# S7CAS-PLEIADES-CARTE-MERE_P01_ETHERNET.net
KiCad netlist of a schematic drawn in Altium Designer
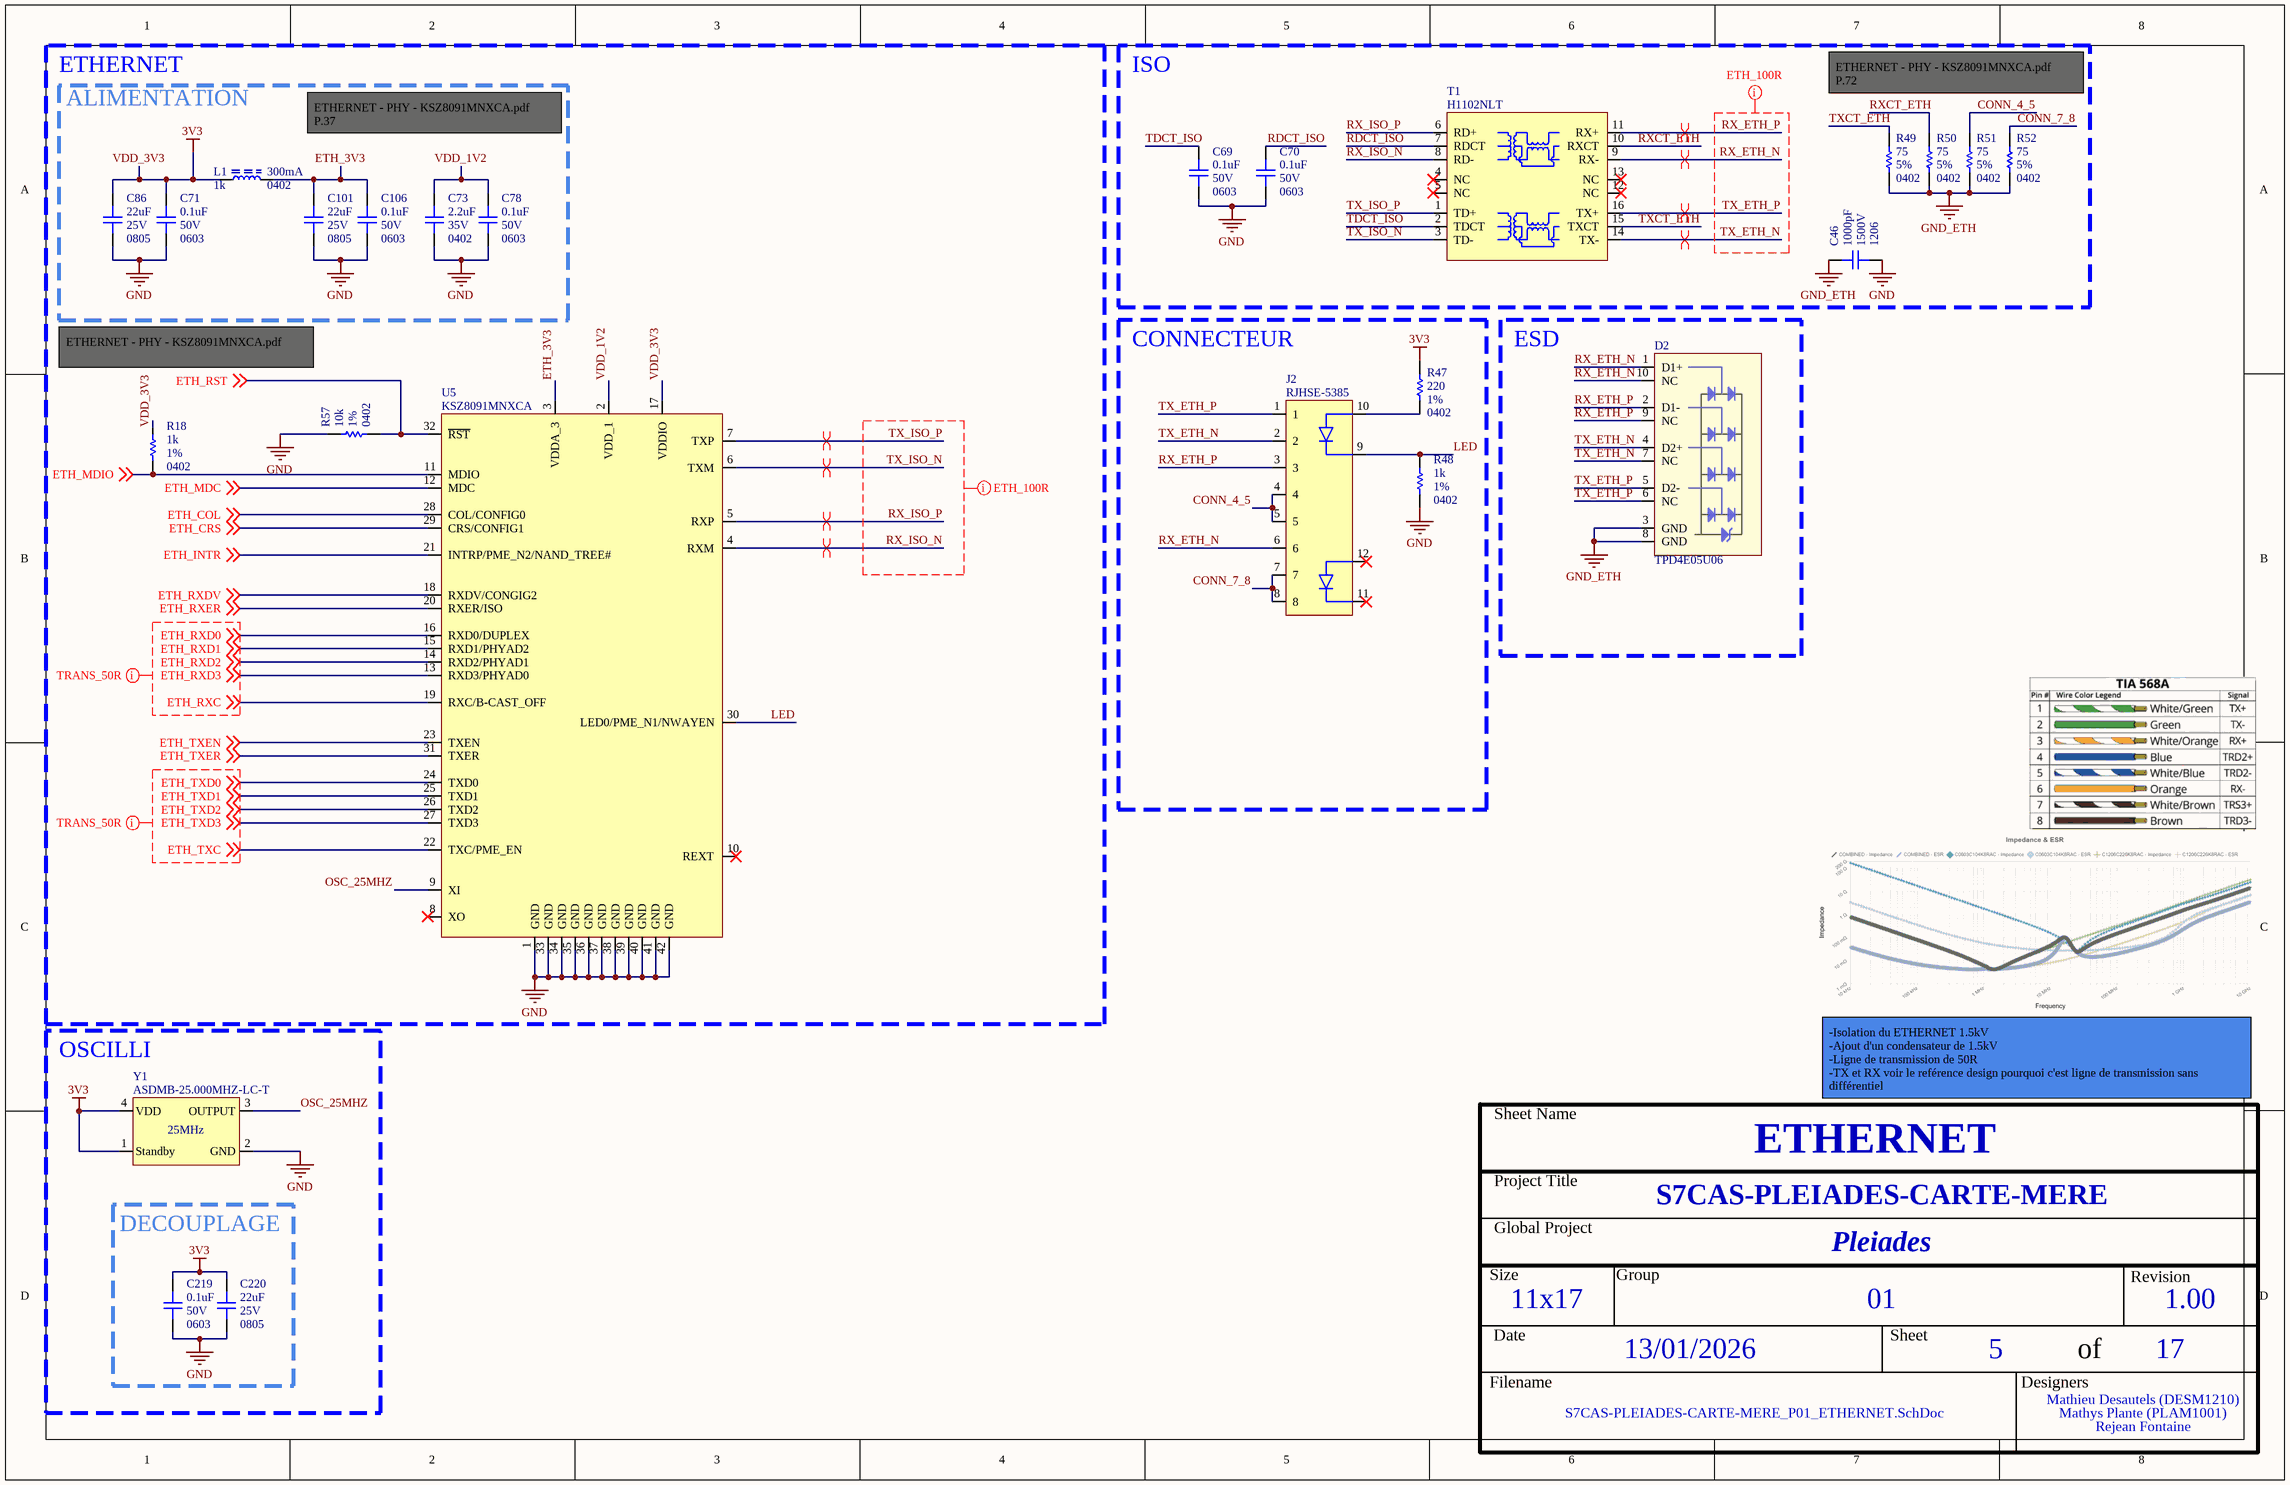
[diagram p0: S7CAS-PLEIADES-CARTE-MERE_P01_ETHERNET.SchDoc]

(export (version "E")
  (design (tool "Eeschema 10.0.6"))
  (components
    (comp (ref "C46")
      (value "1000pF")
      (footprint "CAP_1206")
      (description "1000 pF ±5% 1500V (1.5kV) Ceramic Capacitor C0G, NP0 1206 (3216 Metric)")
      (fields
        (field (name "MFG") "Vishay Vitramon")
        (field (name "MFG PART NUMBER") "VJ1206A102JXRAT5Z")
        (field (name "VOLTAGE") "1500V")
        (field (name "PACKAGE") "1206")
        (field (name "CREATEDBY") "Jonathan Bouchard")
      )
      (libsource (lib "s7cas_lib2023") (part "CAP - 1206"))
    )
    (comp (ref "C69")
      (value "0.1uF")
      (footprint "CAP_0603")
      (description "0.1 µF ±10% 50V Ceramic Capacitor X7R 0603 (1608 Metric)")
      (fields
        (field (name "MFG") "KEMET")
        (field (name "MFG PART NUMBER") "C0603C104K5RACTU")
        (field (name "VOLTAGE") "50V")
        (field (name "PACKAGE") "0603")
        (field (name "CREATEDBY") "Jonathan Bouchard")
      )
      (libsource (lib "s7cas_lib2023") (part "CAP - 0603"))
    )
    (comp (ref "C70")
      (value "0.1uF")
      (footprint "CAP_0603")
      (description "0.1 µF ±10% 50V Ceramic Capacitor X7R 0603 (1608 Metric)")
      (fields
        (field (name "MFG") "KEMET")
        (field (name "MFG PART NUMBER") "C0603C104K5RACTU")
        (field (name "VOLTAGE") "50V")
        (field (name "PACKAGE") "0603")
        (field (name "CREATEDBY") "Jonathan Bouchard")
      )
      (libsource (lib "s7cas_lib2023") (part "CAP - 0603"))
    )
    (comp (ref "C71")
      (value "0.1uF")
      (footprint "CAP_0603")
      (description "0.1 µF ±10% 50V Ceramic Capacitor X7R 0603 (1608 Metric)")
      (fields
        (field (name "MFG") "KEMET")
        (field (name "MFG PART NUMBER") "C0603C104K5RACTU")
        (field (name "VOLTAGE") "50V")
        (field (name "PACKAGE") "0603")
        (field (name "CREATEDBY") "Jonathan Bouchard")
      )
      (libsource (lib "s7cas_lib2023") (part "CAP - 0603"))
    )
    (comp (ref "C73")
      (value "2.2uF")
      (footprint "CAP_0402")
      (description "2.2 µF ±10% 35V Ceramic Capacitor X5R 0402 (1005 Metric)")
      (fields
        (field (name "MFG") "Murata Electronics")
        (field (name "MFG PART NUMBER") "GRM155R6YA225KE11D")
        (field (name "VOLTAGE") "35V")
        (field (name "PACKAGE") "0402")
        (field (name "CREATEDBY") "Jonathan Bouchard")
      )
      (libsource (lib "s7cas_lib2023") (part "CAP - 0402"))
    )
    (comp (ref "C78")
      (value "0.1uF")
      (footprint "CAP_0603")
      (description "0.1 µF ±10% 50V Ceramic Capacitor X7R 0603 (1608 Metric)")
      (fields
        (field (name "MFG") "KEMET")
        (field (name "MFG PART NUMBER") "C0603C104K5RACTU")
        (field (name "VOLTAGE") "50V")
        (field (name "PACKAGE") "0603")
        (field (name "CREATEDBY") "Jonathan Bouchard")
      )
      (libsource (lib "s7cas_lib2023") (part "CAP - 0603"))
    )
    (comp (ref "C86")
      (value "22uF")
      (footprint "CAP_0805")
      (description "22 µF ±20% 25V Ceramic Capacitor X5R 0805 (2012 Metric)")
      (fields
        (field (name "MFG") "Samsung Electro-Mechanics")
        (field (name "MFG PART NUMBER") "CL21A226MAYNNNE")
        (field (name "VOLTAGE") "25V")
        (field (name "PACKAGE") "0805")
        (field (name "CREATEDBY") "Jonathan Bouchard")
      )
      (libsource (lib "s7cas_lib2023") (part "CAP - 0805"))
    )
    (comp (ref "C101")
      (value "22uF")
      (footprint "CAP_0805")
      (description "22 µF ±20% 25V Ceramic Capacitor X5R 0805 (2012 Metric)")
      (fields
        (field (name "MFG") "Samsung Electro-Mechanics")
        (field (name "MFG PART NUMBER") "CL21A226MAYNNNE")
        (field (name "VOLTAGE") "25V")
        (field (name "PACKAGE") "0805")
        (field (name "CREATEDBY") "Jonathan Bouchard")
      )
      (libsource (lib "s7cas_lib2023") (part "CAP - 0805"))
    )
    (comp (ref "C106")
      (value "0.1uF")
      (footprint "CAP_0603")
      (description "0.1 µF ±10% 50V Ceramic Capacitor X7R 0603 (1608 Metric)")
      (fields
        (field (name "MFG") "KEMET")
        (field (name "MFG PART NUMBER") "C0603C104K5RACTU")
        (field (name "VOLTAGE") "50V")
        (field (name "PACKAGE") "0603")
        (field (name "CREATEDBY") "Jonathan Bouchard")
      )
      (libsource (lib "s7cas_lib2023") (part "CAP - 0603"))
    )
    (comp (ref "C219")
      (value "0.1uF")
      (footprint "CAP_0603")
      (description "0.1 µF ±10% 50V Ceramic Capacitor X7R 0603 (1608 Metric)")
      (fields
        (field (name "MFG") "KEMET")
        (field (name "MFG PART NUMBER") "C0603C104K5RACTU")
        (field (name "VOLTAGE") "50V")
        (field (name "PACKAGE") "0603")
        (field (name "CREATEDBY") "Jonathan Bouchard")
      )
      (libsource (lib "s7cas_lib2023") (part "CAP - 0603"))
    )
    (comp (ref "C220")
      (value "22uF")
      (footprint "CAP_0805")
      (description "22 µF ±20% 25V Ceramic Capacitor X5R 0805 (2012 Metric)")
      (fields
        (field (name "MFG") "Samsung Electro-Mechanics")
        (field (name "MFG PART NUMBER") "CL21A226MAYNNNE")
        (field (name "VOLTAGE") "25V")
        (field (name "PACKAGE") "0805")
        (field (name "CREATEDBY") "Jonathan Bouchard")
      )
      (libsource (lib "s7cas_lib2023") (part "CAP - 0805"))
    )
    (comp (ref "D2")
      (value "TPD4E05U06")
      (footprint "TVS_DATA_TPD4E05U06")
      (description "TVS - TVS DIODE 5.5VWM 14VC - 10SON")
      (fields
        (field (name "MFG PART NUMBER") "TPD4E05U06DQAR")
        (field (name "CREATEDBY/DATE") "Olivier Bernard / 12/3/2018")
        (field (name "VERIFIEDBY") "Caroline Paulin / 4 juillet 2018")
      )
      (libsource (lib "s7cas_lib2023") (part "TVS_DATA_TPD4E05U06"))
    )
    (comp (ref "J2")
      (value "RJHSE-5385")
      (footprint "CONN_ETHERNET_RJHSE-5385")
      (description "CONN - MOD JACK RJ45 R/A ETHERNET - TH")
      (fields (field (name "MFG") "Amphenol") (field (name "CREATEDBY") "Jonathan Bouchard"))
      (libsource (lib "s7cas_lib2023") (part "CONN_ETHERNET_RJHSE-5385"))
    )
    (comp (ref "L1")
      (value "1k")
      (footprint "FER_0402")
      (description "1 kOhms @ 100 MHz 1 Ferrite Bead 0402 (1005 Metric) 300mA 650mOhm")
      (fields
        (field (name "MFG") "Murata Electronics")
        (field (name "MFG PART NUMBER") "BLM15AG102SN1D")
        (field (name "CURRENT") "300mA")
        (field (name "PACKAGE") "0402")
        (field (name "CREATEDBY") "Jonathan Bouchard")
      )
      (libsource (lib "s7cas_lib2023") (part "FER - 0402"))
    )
    (comp (ref "R18")
      (value "1k")
      (footprint "RES_0402")
      (description "1 kOhms ±1% 0.1W, 1/10W Chip Resistor 0402 (1005 Metric) Automotive AEC-Q200 Thick Film")
      (fields
        (field (name "VOLTAGE") "50V")
        (field (name "MFG") "Panasonic Electronic Components")
        (field (name "PACKAGE") "0402")
        (field (name "PRECISION") "1%")
        (field (name "CREATEDBY") "Jonathan Bouchard")
      )
      (libsource (lib "s7cas_lib2023") (part "RES - 0402"))
    )
    (comp (ref "R47")
      (value "220")
      (footprint "RES_0402")
      (description "220 Ohms ±1% 0.1W, 1/10W Chip Resistor 0402 (1005 Metric) Automotive AEC-Q200 Thick Film220")
      (fields
        (field (name "VOLTAGE") "50V")
        (field (name "MFG") "Panasonic Electronic Components")
        (field (name "PACKAGE") "0402")
        (field (name "PRECISION") "1%")
        (field (name "CREATEDBY") "Jonathan Bouchard")
      )
      (libsource (lib "s7cas_lib2023") (part "RES - 0402"))
    )
    (comp (ref "R48")
      (value "1k")
      (footprint "RES_0402")
      (description "1 kOhms ±1% 0.1W, 1/10W Chip Resistor 0402 (1005 Metric) Automotive AEC-Q200 Thick Film")
      (fields
        (field (name "VOLTAGE") "50V")
        (field (name "MFG") "Panasonic Electronic Components")
        (field (name "PACKAGE") "0402")
        (field (name "PRECISION") "1%")
        (field (name "CREATEDBY") "Jonathan Bouchard")
      )
      (libsource (lib "s7cas_lib2023") (part "RES - 0402"))
    )
    (comp (ref "R49")
      (value "75")
      (footprint "RES_0402")
      (description "75 Ohms ±5% 0.063W, 1/16W Chip Resistor 0402 (1005 Metric) Moisture Resistant Thick Film")
      (fields
        (field (name "VOLTAGE") "50V")
        (field (name "MFG") "YAGEO")
        (field (name "PACKAGE") "0402")
        (field (name "PRECISION") "5%")
        (field (name "CREATEDBY") "Jonathan Bouchard")
      )
      (libsource (lib "s7cas_lib2023") (part "RES - 0402"))
    )
    (comp (ref "R50")
      (value "75")
      (footprint "RES_0402")
      (description "75 Ohms ±5% 0.063W, 1/16W Chip Resistor 0402 (1005 Metric) Moisture Resistant Thick Film")
      (fields
        (field (name "VOLTAGE") "50V")
        (field (name "MFG") "YAGEO")
        (field (name "PACKAGE") "0402")
        (field (name "PRECISION") "5%")
        (field (name "CREATEDBY") "Jonathan Bouchard")
      )
      (libsource (lib "s7cas_lib2023") (part "RES - 0402"))
    )
    (comp (ref "R51")
      (value "75")
      (footprint "RES_0402")
      (description "75 Ohms ±5% 0.063W, 1/16W Chip Resistor 0402 (1005 Metric) Moisture Resistant Thick Film")
      (fields
        (field (name "VOLTAGE") "50V")
        (field (name "MFG") "YAGEO")
        (field (name "PACKAGE") "0402")
        (field (name "PRECISION") "5%")
        (field (name "CREATEDBY") "Jonathan Bouchard")
      )
      (libsource (lib "s7cas_lib2023") (part "RES - 0402"))
    )
    (comp (ref "R52")
      (value "75")
      (footprint "RES_0402")
      (description "75 Ohms ±5% 0.063W, 1/16W Chip Resistor 0402 (1005 Metric) Moisture Resistant Thick Film")
      (fields
        (field (name "VOLTAGE") "50V")
        (field (name "MFG") "YAGEO")
        (field (name "PACKAGE") "0402")
        (field (name "PRECISION") "5%")
        (field (name "CREATEDBY") "Jonathan Bouchard")
      )
      (libsource (lib "s7cas_lib2023") (part "RES - 0402"))
    )
    (comp (ref "R57")
      (value "10k")
      (footprint "RES_0402")
      (description "10 kOhms ±1% 0.063W, 1/16W Chip Resistor 0402 (1005 Metric) Automotive AEC-Q200 Thick Film")
      (fields
        (field (name "VOLTAGE") "75V")
        (field (name "MFG PART NUMBER") "RMCF0402FT10K0")
        (field (name "PACKAGE") "0402")
        (field (name "PRECISION") "1%")
        (field (name "CREATEDBY") "Jonathan Bouchard")
      )
      (libsource (lib "s7cas_lib2023") (part "RES - 0402"))
    )
    (comp (ref "T1")
      (value "H1102NLT")
      (footprint "TRANSFO_H1102NLT")
      (description "TRANSFO - ETHERNET 10/100B-TX - SMD-16")
      (fields (field (name "MFG") "Pulse Eng.") (field (name "CREATEDBY") "Jonathan Bouchard"))
      (libsource (lib "s7cas_lib2023") (part "TRANSFO_H1102NLT"))
    )
    (comp (ref "U5")
      (value "KSZ8091MNXCA")
      (footprint "COM_ETH_PHY_KSZ8091MNXCA")
      (description "COM - ETHERNET PHY 10/100 - QFN-32")
      (fields
        (field (name "VOLTAGE") "1.8V, 2.5V, 3.3V")
        (field (name "MFG") "Micrel")
        (field (name "CREATEDBY") "Jonathan Bouchard")
      )
      (libsource (lib "s7cas_lib2023") (part "COM_ETH_PHY_KSZ8091MNXCA"))
    )
    (comp (ref "Y1")
      (value "ASDMB-25.000MHZ-LC-T")
      (footprint "OSC_ASDMB-25.000MHZ-LC-T")
      (description "OSC - 25MHz XO (Standard) LVCMOS - 4-SMD, No Lead")
      (fields
        (field (name "TOLERANCE") "±50ppm")
        (field (name "CREATEDBY/DATE") "Joël Lemay 2019-03-29")
        (field (name "VERIFIEDBY") "C. Paulin - 29 mai 2019")
      )
      (libsource (lib "s7cas_lib2023") (part "OSC_ASDMB-25.000MHZ-LC-T"))
    )
  )
  (nets
    (net (code "1") (name "/CONN_4_5") (class "Default")
      (node (ref "J2") (pin "4") (pinfunction "4_4") (pintype "passive"))
      (node (ref "J2") (pin "5") (pinfunction "5_5") (pintype "passive"))
      (node (ref "R51") (pin "2") (pinfunction "2_2") (pintype "passive"))
    )
    (net (code "2") (name "/CONN_7_8") (class "Default")
      (node (ref "J2") (pin "7") (pinfunction "7_7") (pintype "passive"))
      (node (ref "J2") (pin "8") (pinfunction "8_8") (pintype "passive"))
      (node (ref "R52") (pin "2") (pinfunction "2_2") (pintype "passive"))
    )
    (net (code "3") (name "/ETH_3V3") (class "Default")
      (node (ref "C101") (pin "2") (pinfunction "2_2") (pintype "passive"))
      (node (ref "C106") (pin "2") (pinfunction "2_2") (pintype "passive"))
      (node (ref "L1") (pin "1") (pinfunction "1_1") (pintype "passive"))
      (node (ref "U5") (pin "3") (pinfunction "VDDA_3_3") (pintype "power_in"))
    )
    (net (code "4") (name "/LED") (class "Default")
      (node (ref "J2") (pin "9") (pinfunction "LED1_K_9") (pintype "passive"))
      (node (ref "R48") (pin "2") (pinfunction "2_2") (pintype "passive"))
      (node (ref "U5") (pin "30") (pinfunction "LED0/PME_N1/NWAYEN_30") (pintype "passive"))
    )
    (net (code "5") (name "/OSC_25MHZ") (class "Default")
      (node (ref "U5") (pin "9") (pinfunction "XI_9") (pintype "passive"))
      (node (ref "Y1") (pin "3") (pinfunction "OUTPUT_3") (pintype "passive"))
    )
    (net (code "6") (name "/RDCT_ISO") (class "Default")
      (node (ref "C70") (pin "2") (pinfunction "2_2") (pintype "passive"))
      (node (ref "T1") (pin "7") (pinfunction "RDCT_7") (pintype "passive"))
    )
    (net (code "7") (name "/RXCT_ETH") (class "Default")
      (node (ref "R50") (pin "2") (pinfunction "2_2") (pintype "passive"))
      (node (ref "T1") (pin "10") (pinfunction "RXCT_10") (pintype "passive"))
    )
    (net (code "8") (name "/RX_ETH_N") (class "Default")
      (node (ref "D2") (pin "1") (pinfunction "D1+_1") (pintype "passive"))
      (node (ref "D2") (pin "10") (pinfunction "NC_10") (pintype "passive"))
      (node (ref "J2") (pin "6") (pinfunction "6_6") (pintype "passive"))
      (node (ref "T1") (pin "9") (pinfunction "RX-_9") (pintype "passive"))
    )
    (net (code "9") (name "/RX_ETH_P") (class "Default")
      (node (ref "D2") (pin "2") (pinfunction "D1-_2") (pintype "passive"))
      (node (ref "D2") (pin "9") (pinfunction "NC_9") (pintype "passive"))
      (node (ref "J2") (pin "3") (pinfunction "3_3") (pintype "passive"))
      (node (ref "T1") (pin "11") (pinfunction "RX+_11") (pintype "passive"))
    )
    (net (code "10") (name "/RX_ISO_N") (class "Default")
      (node (ref "T1") (pin "8") (pinfunction "RD-_8") (pintype "passive"))
      (node (ref "U5") (pin "4") (pinfunction "RXM_4") (pintype "passive"))
    )
    (net (code "11") (name "/RX_ISO_P") (class "Default")
      (node (ref "T1") (pin "6") (pinfunction "RD+_6") (pintype "passive"))
      (node (ref "U5") (pin "5") (pinfunction "RXP_5") (pintype "passive"))
    )
    (net (code "12") (name "/TDCT_ISO") (class "Default")
      (node (ref "C69") (pin "2") (pinfunction "2_2") (pintype "passive"))
      (node (ref "T1") (pin "2") (pinfunction "TDCT_2") (pintype "passive"))
    )
    (net (code "13") (name "/TXCT_ETH") (class "Default")
      (node (ref "R49") (pin "2") (pinfunction "2_2") (pintype "passive"))
      (node (ref "T1") (pin "15") (pinfunction "TXCT_15") (pintype "passive"))
    )
    (net (code "14") (name "/TX_ETH_N") (class "Default")
      (node (ref "D2") (pin "4") (pinfunction "D2+_4") (pintype "passive"))
      (node (ref "D2") (pin "7") (pinfunction "NC_7") (pintype "passive"))
      (node (ref "J2") (pin "2") (pinfunction "2_2") (pintype "passive"))
      (node (ref "T1") (pin "14") (pinfunction "TX-_14") (pintype "passive"))
    )
    (net (code "15") (name "/TX_ETH_P") (class "Default")
      (node (ref "D2") (pin "5") (pinfunction "D2-_5") (pintype "passive"))
      (node (ref "D2") (pin "6") (pinfunction "NC_6") (pintype "passive"))
      (node (ref "J2") (pin "1") (pinfunction "1_1") (pintype "passive"))
      (node (ref "T1") (pin "16") (pinfunction "TX+_16") (pintype "passive"))
    )
    (net (code "16") (name "/TX_ISO_N") (class "Default")
      (node (ref "T1") (pin "3") (pinfunction "TD-_3") (pintype "passive"))
      (node (ref "U5") (pin "6") (pinfunction "TXM_6") (pintype "passive"))
    )
    (net (code "17") (name "/TX_ISO_P") (class "Default")
      (node (ref "T1") (pin "1") (pinfunction "TD+_1") (pintype "passive"))
      (node (ref "U5") (pin "7") (pinfunction "TXP_7") (pintype "passive"))
    )
    (net (code "18") (name "/VDD_1V2") (class "Default")
      (node (ref "C73") (pin "2") (pinfunction "2_2") (pintype "passive"))
      (node (ref "C78") (pin "2") (pinfunction "2_2") (pintype "passive"))
      (node (ref "U5") (pin "2") (pinfunction "VDD_1_2") (pintype "power_in"))
    )
    (net (code "19") (name "3V3") (class "Default")
      (node (ref "C219") (pin "2") (pinfunction "2_2") (pintype "passive"))
      (node (ref "C220") (pin "2") (pinfunction "2_2") (pintype "passive"))
      (node (ref "C71") (pin "2") (pinfunction "2_2") (pintype "passive"))
      (node (ref "C86") (pin "2") (pinfunction "2_2") (pintype "passive"))
      (node (ref "L1") (pin "2") (pinfunction "2_2") (pintype "passive"))
      (node (ref "R18") (pin "2") (pinfunction "2_2") (pintype "passive"))
      (node (ref "R47") (pin "2") (pinfunction "2_2") (pintype "passive"))
      (node (ref "U5") (pin "17") (pinfunction "VDDIO_17") (pintype "power_in"))
      (node (ref "Y1") (pin "1") (pinfunction "Standby_1") (pintype "passive"))
      (node (ref "Y1") (pin "4") (pinfunction "VDD_4") (pintype "passive"))
    )
    (net (code "20") (name "ETH_COL") (class "Default")
      (node (ref "U5") (pin "28") (pinfunction "COL/CONFIG0_28") (pintype "passive"))
    )
    (net (code "21") (name "ETH_CRS") (class "Default")
      (node (ref "U5") (pin "29") (pinfunction "CRS/CONFIG1_29") (pintype "passive"))
    )
    (net (code "22") (name "ETH_INTR") (class "Default")
      (node (ref "U5") (pin "21") (pinfunction "INTRP/PME_N2/NAND_TREE#_21") (pintype "passive"))
    )
    (net (code "23") (name "ETH_MDC") (class "Default")
      (node (ref "U5") (pin "12") (pinfunction "MDC_12") (pintype "passive"))
    )
    (net (code "24") (name "ETH_MDIO") (class "Default")
      (node (ref "R18") (pin "1") (pinfunction "1_1") (pintype "passive"))
      (node (ref "U5") (pin "11") (pinfunction "MDIO_11") (pintype "passive"))
    )
    (net (code "25") (name "ETH_RST") (class "Default")
      (node (ref "R57") (pin "2") (pinfunction "2_2") (pintype "passive"))
      (node (ref "U5") (pin "32") (pinfunction "RST_32") (pintype "passive"))
    )
    (net (code "26") (name "ETH_RXC") (class "Default")
      (node (ref "U5") (pin "19") (pinfunction "RXC/B-CAST_OFF_19") (pintype "passive"))
    )
    (net (code "27") (name "ETH_RXD0") (class "Default")
      (node (ref "U5") (pin "16") (pinfunction "RXD0/DUPLEX_16") (pintype "passive"))
    )
    (net (code "28") (name "ETH_RXD1") (class "Default")
      (node (ref "U5") (pin "15") (pinfunction "RXD1/PHYAD2_15") (pintype "passive"))
    )
    (net (code "29") (name "ETH_RXD2") (class "Default")
      (node (ref "U5") (pin "14") (pinfunction "RXD2/PHYAD1_14") (pintype "passive"))
    )
    (net (code "30") (name "ETH_RXD3") (class "Default")
      (node (ref "U5") (pin "13") (pinfunction "RXD3/PHYAD0_13") (pintype "passive"))
    )
    (net (code "31") (name "ETH_RXDV") (class "Default")
      (node (ref "U5") (pin "18") (pinfunction "RXDV/CONGIG2_18") (pintype "passive"))
    )
    (net (code "32") (name "ETH_RXER") (class "Default")
      (node (ref "U5") (pin "20") (pinfunction "RXER/ISO_20") (pintype "passive"))
    )
    (net (code "33") (name "ETH_TXC") (class "Default")
      (node (ref "U5") (pin "22") (pinfunction "TXC/PME_EN_22") (pintype "passive"))
    )
    (net (code "34") (name "ETH_TXD0") (class "Default")
      (node (ref "U5") (pin "24") (pinfunction "TXD0_24") (pintype "passive"))
    )
    (net (code "35") (name "ETH_TXD1") (class "Default")
      (node (ref "U5") (pin "25") (pinfunction "TXD1_25") (pintype "passive"))
    )
    (net (code "36") (name "ETH_TXD2") (class "Default")
      (node (ref "U5") (pin "26") (pinfunction "TXD2_26") (pintype "passive"))
    )
    (net (code "37") (name "ETH_TXD3") (class "Default")
      (node (ref "U5") (pin "27") (pinfunction "TXD3_27") (pintype "passive"))
    )
    (net (code "38") (name "ETH_TXEN") (class "Default")
      (node (ref "U5") (pin "23") (pinfunction "TXEN_23") (pintype "passive"))
    )
    (net (code "39") (name "ETH_TXER") (class "Default")
      (node (ref "U5") (pin "31") (pinfunction "TXER_31") (pintype "passive"))
    )
    (net (code "40") (name "GND") (class "Default")
      (node (ref "C101") (pin "1") (pinfunction "1_1") (pintype "passive"))
      (node (ref "C106") (pin "1") (pinfunction "1_1") (pintype "passive"))
      (node (ref "C219") (pin "1") (pinfunction "1_1") (pintype "passive"))
      (node (ref "C220") (pin "1") (pinfunction "1_1") (pintype "passive"))
      (node (ref "C46") (pin "1") (pinfunction "1_1") (pintype "passive"))
      (node (ref "C69") (pin "1") (pinfunction "1_1") (pintype "passive"))
      (node (ref "C70") (pin "1") (pinfunction "1_1") (pintype "passive"))
      (node (ref "C71") (pin "1") (pinfunction "1_1") (pintype "passive"))
      (node (ref "C73") (pin "1") (pinfunction "1_1") (pintype "passive"))
      (node (ref "C78") (pin "1") (pinfunction "1_1") (pintype "passive"))
      (node (ref "C86") (pin "1") (pinfunction "1_1") (pintype "passive"))
      (node (ref "R48") (pin "1") (pinfunction "1_1") (pintype "passive"))
      (node (ref "R57") (pin "1") (pinfunction "1_1") (pintype "passive"))
      (node (ref "U5") (pin "1") (pinfunction "GND_1") (pintype "passive"))
      (node (ref "U5") (pin "33") (pinfunction "GND_33") (pintype "passive"))
      (node (ref "U5") (pin "34") (pinfunction "GND_34") (pintype "passive"))
      (node (ref "U5") (pin "35") (pinfunction "GND_35") (pintype "passive"))
      (node (ref "U5") (pin "36") (pinfunction "GND_36") (pintype "passive"))
      (node (ref "U5") (pin "37") (pinfunction "GND_37") (pintype "passive"))
      (node (ref "U5") (pin "38") (pinfunction "GND_38") (pintype "passive"))
      (node (ref "U5") (pin "39") (pinfunction "GND_39") (pintype "passive"))
      (node (ref "U5") (pin "40") (pinfunction "GND_40") (pintype "passive"))
      (node (ref "U5") (pin "41") (pinfunction "GND_41") (pintype "passive"))
      (node (ref "U5") (pin "42") (pinfunction "GND_42") (pintype "passive"))
      (node (ref "Y1") (pin "2") (pinfunction "GND_2") (pintype "passive"))
    )
    (net (code "41") (name "GND_ETH") (class "Default")
      (node (ref "C46") (pin "2") (pinfunction "2_2") (pintype "passive"))
      (node (ref "D2") (pin "3") (pinfunction "GND_3") (pintype "passive"))
      (node (ref "D2") (pin "8") (pinfunction "GND_8") (pintype "passive"))
      (node (ref "R49") (pin "1") (pinfunction "1_1") (pintype "passive"))
      (node (ref "R50") (pin "1") (pinfunction "1_1") (pintype "passive"))
      (node (ref "R51") (pin "1") (pinfunction "1_1") (pintype "passive"))
      (node (ref "R52") (pin "1") (pinfunction "1_1") (pintype "passive"))
    )
    (net (code "42") (name "Net-(J2-LED1_A)") (class "Default")
      (node (ref "J2") (pin "10") (pinfunction "LED1_A_10") (pintype "passive"))
      (node (ref "R47") (pin "1") (pinfunction "1_1") (pintype "passive"))
    )
    (net (code "43") (name "unconnected-(J2-LED2_A-Pad12)") (class "Default")
      (node (ref "J2") (pin "12") (pinfunction "LED2_A_12") (pintype "passive+no_connect"))
    )
    (net (code "44") (name "unconnected-(J2-LED2_K-Pad11)") (class "Default")
      (node (ref "J2") (pin "11") (pinfunction "LED2_K_11") (pintype "passive+no_connect"))
    )
    (net (code "45") (name "unconnected-(T1-NC-Pad4)") (class "Default")
      (node (ref "T1") (pin "4") (pinfunction "NC_4") (pintype "passive+no_connect"))
    )
    (net (code "46") (name "unconnected-(T1-NC-Pad5)") (class "Default")
      (node (ref "T1") (pin "5") (pinfunction "NC_5") (pintype "passive+no_connect"))
    )
    (net (code "47") (name "unconnected-(T1-NC-Pad12)") (class "Default")
      (node (ref "T1") (pin "12") (pinfunction "NC_12") (pintype "passive+no_connect"))
    )
    (net (code "48") (name "unconnected-(T1-NC-Pad13)") (class "Default")
      (node (ref "T1") (pin "13") (pinfunction "NC_13") (pintype "passive+no_connect"))
    )
    (net (code "49") (name "unconnected-(U5-REXT-Pad10)") (class "Default")
      (node (ref "U5") (pin "10") (pinfunction "REXT_10") (pintype "passive+no_connect"))
    )
    (net (code "50") (name "unconnected-(U5-XO-Pad8)") (class "Default")
      (node (ref "U5") (pin "8") (pinfunction "XO_8") (pintype "passive+no_connect"))
    )
  )
)
